# Oscar_MainBoard_Temperature.net
KiCad netlist of a schematic drawn in Altium Designer
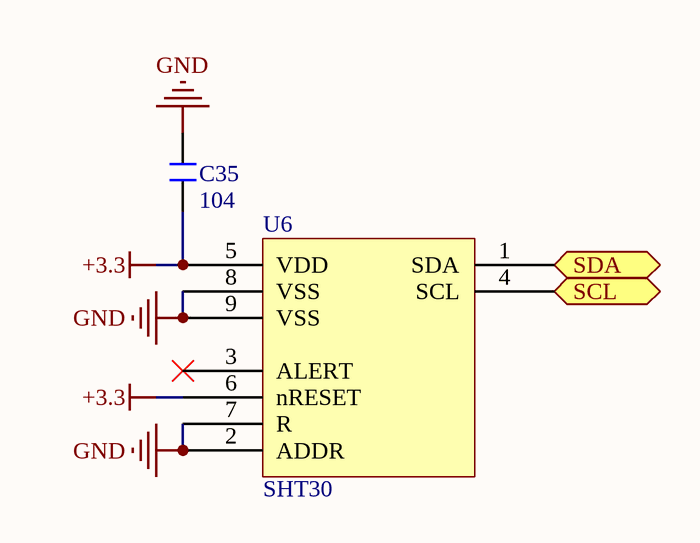
[diagram p0: Oscar_MainBoard_Temperature.SchDoc]

(export (version "E")
  (design (tool "Eeschema 10.0.6"))
  (components
    (comp (ref "C35")
      (value "104")
      (footprint "C 0402_L")
      (description "贴片电容")
      (libsource (lib "0.1 - 电阻-电容-电感") (part "C"))
    )
    (comp (ref "U6")
      (value "SHT30")
      (footprint "DFN-8_L2.5-W2.5-P0.50-BL-EP")
      (libsource (lib "1.2 - 传感元件") (part "SHT30"))
    )
  )
  (nets
    (net (code "1") (name "+3.3") (class "Default")
      (node (ref "C35") (pin "1") (pinfunction "1_1") (pintype "passive"))
      (node (ref "U6") (pin "5") (pinfunction "VDD_5") (pintype "passive"))
      (node (ref "U6") (pin "6") (pinfunction "nRESET_6") (pintype "passive"))
    )
    (net (code "2") (name "/SCL") (class "Default")
      (node (ref "U6") (pin "4") (pinfunction "SCL_4") (pintype "passive"))
    )
    (net (code "3") (name "/SDA") (class "Default")
      (node (ref "U6") (pin "1") (pinfunction "SDA_1") (pintype "passive"))
    )
    (net (code "4") (name "GND") (class "Default")
      (node (ref "C35") (pin "2") (pinfunction "2_2") (pintype "passive"))
      (node (ref "U6") (pin "2") (pinfunction "ADDR_2") (pintype "passive"))
      (node (ref "U6") (pin "7") (pinfunction "R_7") (pintype "passive"))
      (node (ref "U6") (pin "8") (pinfunction "VSS_8") (pintype "passive"))
      (node (ref "U6") (pin "9") (pinfunction "VSS_9") (pintype "passive"))
    )
    (net (code "5") (name "unconnected-(U6-ALERT-Pad3)") (class "Default")
      (node (ref "U6") (pin "3") (pinfunction "ALERT_3") (pintype "passive+no_connect"))
    )
  )
)
